# HeaterThermostatV1.net
KiCad netlist of a schematic drawn in EAGLE
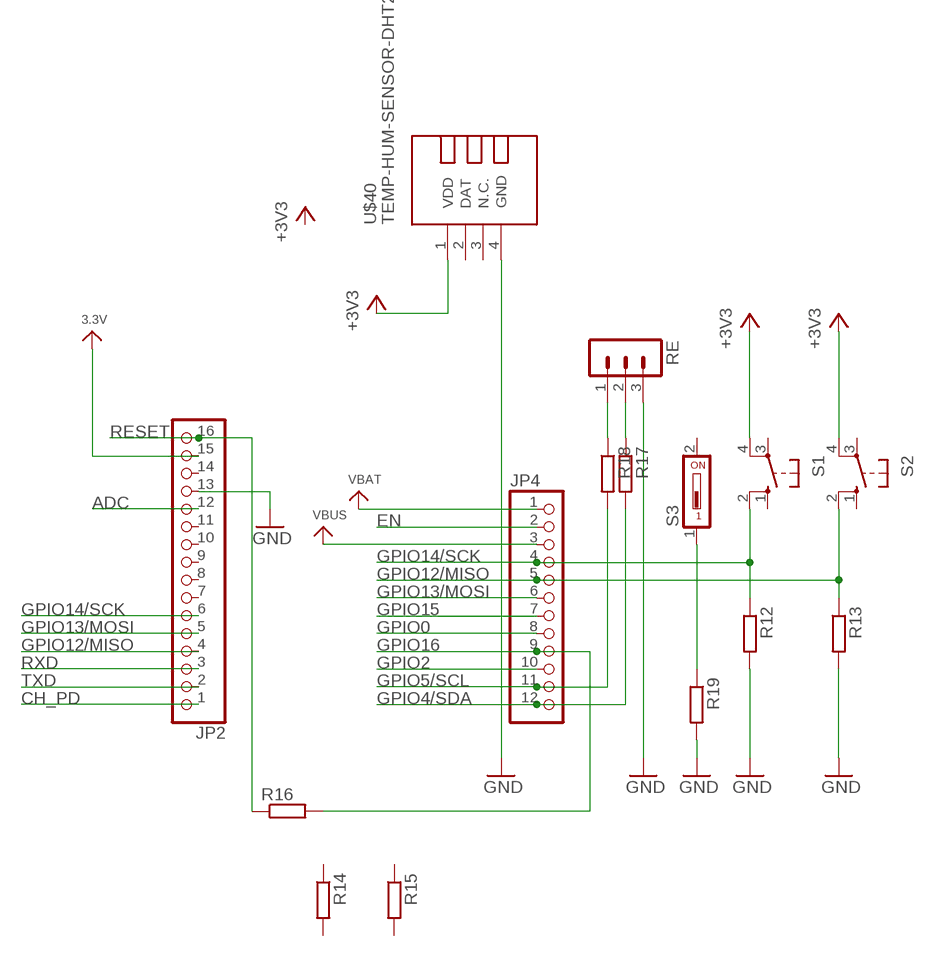
[diagram p0: schematic, sheet 1]

(export (version "E")
  (design (tool "Eeschema 10.0.6"))
  (components
    (comp (ref "JP2")
      (value "HEADER-1X16ROUND")
      (footprint "eagle-import:1X16_ROUND")
      (libsource (lib "eagle-import") (part "HEADER-1X16ROUND"))
    )
    (comp (ref "JP4")
      (value "HEADER-1X12")
      (footprint "eagle-import:1X12_ROUND")
      (libsource (lib "eagle-import") (part "HEADER-1X12"))
    )
    (comp (ref "R12")
      (value "R-EU_0207/10")
      (footprint "eagle-import:0207_10")
      (libsource (lib "eagle-import") (part "R-EU_0207/10"))
    )
    (comp (ref "R13")
      (value "R-EU_0207/10")
      (footprint "eagle-import:0207_10")
      (libsource (lib "eagle-import") (part "R-EU_0207/10"))
    )
    (comp (ref "R14")
      (value "R-EU_0207/10")
      (footprint "eagle-import:0207_10")
      (libsource (lib "eagle-import") (part "R-EU_0207/10"))
    )
    (comp (ref "R15")
      (value "R-EU_0207/10")
      (footprint "eagle-import:0207_10")
      (libsource (lib "eagle-import") (part "R-EU_0207/10"))
    )
    (comp (ref "R16")
      (value "R-EU_0207/10")
      (footprint "eagle-import:0207_10")
      (libsource (lib "eagle-import") (part "R-EU_0207/10"))
    )
    (comp (ref "R17")
      (value "R-EU_0207/10")
      (footprint "eagle-import:0207_10")
      (libsource (lib "eagle-import") (part "R-EU_0207/10"))
    )
    (comp (ref "R18")
      (value "R-EU_0207/10")
      (footprint "eagle-import:0207_10")
      (libsource (lib "eagle-import") (part "R-EU_0207/10"))
    )
    (comp (ref "R19")
      (value "R-EU_0207/10")
      (footprint "eagle-import:0207_10")
      (libsource (lib "eagle-import") (part "R-EU_0207/10"))
    )
    (comp (ref "RE")
      (value "MA03-1")
      (footprint "eagle-import:MA03-1")
      (libsource (lib "eagle-import") (part "MA03-1"))
    )
    (comp (ref "S1")
      (value "10-XX")
      (footprint "eagle-import:B3F-10XX")
      (fields (field (name "MPN") "B3F-1000"))
      (libsource (lib "eagle-import") (part "10-XX"))
    )
    (comp (ref "S2")
      (value "10-XX")
      (footprint "eagle-import:B3F-10XX")
      (fields (field (name "MPN") "B3F-1000"))
      (libsource (lib "eagle-import") (part "10-XX"))
    )
    (comp (ref "S3")
      (value "DS01")
      (footprint "eagle-import:DS-01")
      (libsource (lib "eagle-import") (part "DS01"))
    )
    (comp (ref "U$40")
      (value "TEMP-HUM-SENSOR-DHT22")
      (footprint "eagle-import:TEMP-HUM-SENSOR-DHT22")
      (libsource (lib "eagle-import") (part "TEMP-HUM-SENSOR-DHT22"))
    )
  )
  (nets
    (net (code "1") (name "+3V3") (class "Default")
      (node (ref "S1") (pin "4") (pinfunction "P1_4") (pintype "passive"))
      (node (ref "S2") (pin "4") (pinfunction "P1_4") (pintype "passive"))
      (node (ref "U$40") (pin "1") (pinfunction "VDD_1") (pintype "power_in"))
    )
    (net (code "2") (name "/ADC") (class "Default")
      (node (ref "JP2") (pin "12") (pinfunction "12_12") (pintype "passive"))
    )
    (net (code "3") (name "/CH_PD") (class "Default")
      (node (ref "JP2") (pin "1") (pinfunction "1_1") (pintype "passive"))
    )
    (net (code "4") (name "/EN") (class "Default")
      (node (ref "JP4") (pin "2") (pinfunction "2_2") (pintype "passive"))
    )
    (net (code "5") (name "/GPIO0") (class "Default")
      (node (ref "JP4") (pin "8") (pinfunction "8_8") (pintype "passive"))
    )
    (net (code "6") (name "/GPIO2") (class "Default")
      (node (ref "JP4") (pin "10") (pinfunction "10_10") (pintype "passive"))
    )
    (net (code "7") (name "/GPIO4{slash}SDA") (class "Default")
      (node (ref "JP4") (pin "12") (pinfunction "12_12") (pintype "passive"))
      (node (ref "R17") (pin "2") (pinfunction "2_2") (pintype "passive"))
    )
    (net (code "8") (name "/GPIO5{slash}SCL") (class "Default")
      (node (ref "JP4") (pin "11") (pinfunction "11_11") (pintype "passive"))
      (node (ref "R18") (pin "2") (pinfunction "2_2") (pintype "passive"))
    )
    (net (code "9") (name "/GPIO12{slash}MISO") (class "Default")
      (node (ref "JP2") (pin "4") (pinfunction "4_4") (pintype "passive"))
      (node (ref "JP4") (pin "5") (pinfunction "5_5") (pintype "passive"))
      (node (ref "R13") (pin "1") (pinfunction "1_1") (pintype "passive"))
      (node (ref "S2") (pin "2") (pinfunction "S1_2") (pintype "passive"))
    )
    (net (code "10") (name "/GPIO13{slash}MOSI") (class "Default")
      (node (ref "JP2") (pin "5") (pinfunction "5_5") (pintype "passive"))
      (node (ref "JP4") (pin "6") (pinfunction "6_6") (pintype "passive"))
    )
    (net (code "11") (name "/GPIO14{slash}SCK") (class "Default")
      (node (ref "JP2") (pin "6") (pinfunction "6_6") (pintype "passive"))
      (node (ref "JP4") (pin "4") (pinfunction "4_4") (pintype "passive"))
      (node (ref "R12") (pin "1") (pinfunction "1_1") (pintype "passive"))
      (node (ref "S1") (pin "2") (pinfunction "S1_2") (pintype "passive"))
    )
    (net (code "12") (name "/GPIO15") (class "Default")
      (node (ref "JP4") (pin "7") (pinfunction "7_7") (pintype "passive"))
    )
    (net (code "13") (name "/GPIO16") (class "Default")
      (node (ref "JP4") (pin "9") (pinfunction "9_9") (pintype "passive"))
      (node (ref "R16") (pin "2") (pinfunction "2_2") (pintype "passive"))
    )
    (net (code "14") (name "/RESET") (class "Default")
      (node (ref "JP2") (pin "16") (pinfunction "16_16") (pintype "passive"))
      (node (ref "R16") (pin "1") (pinfunction "1_1") (pintype "passive"))
    )
    (net (code "15") (name "/RXD") (class "Default")
      (node (ref "JP2") (pin "3") (pinfunction "3_3") (pintype "passive"))
    )
    (net (code "16") (name "/TXD") (class "Default")
      (node (ref "JP2") (pin "2") (pinfunction "2_2") (pintype "passive"))
    )
    (net (code "17") (name "3.3V") (class "Default")
      (node (ref "JP2") (pin "15") (pinfunction "15_15") (pintype "passive"))
    )
    (net (code "18") (name "GND") (class "Default")
      (node (ref "JP2") (pin "13") (pinfunction "13_13") (pintype "passive"))
      (node (ref "R12") (pin "2") (pinfunction "2_2") (pintype "passive"))
      (node (ref "R13") (pin "2") (pinfunction "2_2") (pintype "passive"))
      (node (ref "R19") (pin "2") (pinfunction "2_2") (pintype "passive"))
      (node (ref "RE") (pin "3") (pinfunction "3_3") (pintype "passive"))
      (node (ref "U$40") (pin "4") (pinfunction "GND_4") (pintype "power_in"))
    )
    (net (code "19") (name "Net-(R17-Pad1)") (class "Default")
      (node (ref "R17") (pin "1") (pinfunction "1_1") (pintype "passive"))
      (node (ref "RE") (pin "2") (pinfunction "2_2") (pintype "passive"))
    )
    (net (code "20") (name "Net-(R18-Pad1)") (class "Default")
      (node (ref "R18") (pin "1") (pinfunction "1_1") (pintype "passive"))
      (node (ref "RE") (pin "1") (pinfunction "1_1") (pintype "passive"))
    )
    (net (code "21") (name "Net-(R19-Pad1)") (class "Default")
      (node (ref "R19") (pin "1") (pinfunction "1_1") (pintype "passive"))
      (node (ref "S3") (pin "1") (pinfunction "1_1") (pintype "passive"))
    )
    (net (code "22") (name "VBAT") (class "Default")
      (node (ref "JP4") (pin "1") (pinfunction "1_1") (pintype "passive"))
    )
    (net (code "23") (name "VBUS") (class "Default")
      (node (ref "JP4") (pin "3") (pinfunction "3_3") (pintype "passive"))
    )
    (net (code "24") (name "unconnected-(JP2-Pad7)") (class "Default")
      (node (ref "JP2") (pin "7") (pinfunction "7_7") (pintype "passive"))
    )
    (net (code "25") (name "unconnected-(JP2-Pad8)") (class "Default")
      (node (ref "JP2") (pin "8") (pinfunction "8_8") (pintype "passive"))
    )
    (net (code "26") (name "unconnected-(JP2-Pad9)") (class "Default")
      (node (ref "JP2") (pin "9") (pinfunction "9_9") (pintype "passive"))
    )
    (net (code "27") (name "unconnected-(JP2-Pad10)") (class "Default")
      (node (ref "JP2") (pin "10") (pinfunction "10_10") (pintype "passive"))
    )
    (net (code "28") (name "unconnected-(JP2-Pad11)") (class "Default")
      (node (ref "JP2") (pin "11") (pinfunction "11_11") (pintype "passive"))
    )
    (net (code "29") (name "unconnected-(JP2-Pad14)") (class "Default")
      (node (ref "JP2") (pin "14") (pinfunction "14_14") (pintype "passive"))
    )
    (net (code "30") (name "unconnected-(R14-Pad1)") (class "Default")
      (node (ref "R14") (pin "1") (pinfunction "1_1") (pintype "passive"))
    )
    (net (code "31") (name "unconnected-(R14-Pad2)") (class "Default")
      (node (ref "R14") (pin "2") (pinfunction "2_2") (pintype "passive"))
    )
    (net (code "32") (name "unconnected-(R15-Pad1)") (class "Default")
      (node (ref "R15") (pin "1") (pinfunction "1_1") (pintype "passive"))
    )
    (net (code "33") (name "unconnected-(R15-Pad2)") (class "Default")
      (node (ref "R15") (pin "2") (pinfunction "2_2") (pintype "passive"))
    )
    (net (code "34") (name "unconnected-(S1-P-Pad3)") (class "Default")
      (node (ref "S1") (pin "3") (pinfunction "P_3") (pintype "passive"))
    )
    (net (code "35") (name "unconnected-(S1-S-Pad1)") (class "Default")
      (node (ref "S1") (pin "1") (pinfunction "S_1") (pintype "passive"))
    )
    (net (code "36") (name "unconnected-(S2-P-Pad3)") (class "Default")
      (node (ref "S2") (pin "3") (pinfunction "P_3") (pintype "passive"))
    )
    (net (code "37") (name "unconnected-(S2-S-Pad1)") (class "Default")
      (node (ref "S2") (pin "1") (pinfunction "S_1") (pintype "passive"))
    )
    (net (code "38") (name "unconnected-(S3-Pad2)") (class "Default")
      (node (ref "S3") (pin "2") (pinfunction "2_2") (pintype "passive"))
    )
    (net (code "39") (name "unconnected-(U$40-DAT-Pad2)") (class "Default")
      (node (ref "U$40") (pin "2") (pinfunction "DAT_2") (pintype "bidirectional"))
    )
    (net (code "40") (name "unconnected-(U$40-N.C.-Pad3)") (class "Default")
      (node (ref "U$40") (pin "3") (pinfunction "N.C._3") (pintype "passive"))
    )
  )
)
